# l298.net
KiCad netlist of a schematic drawn in EAGLE
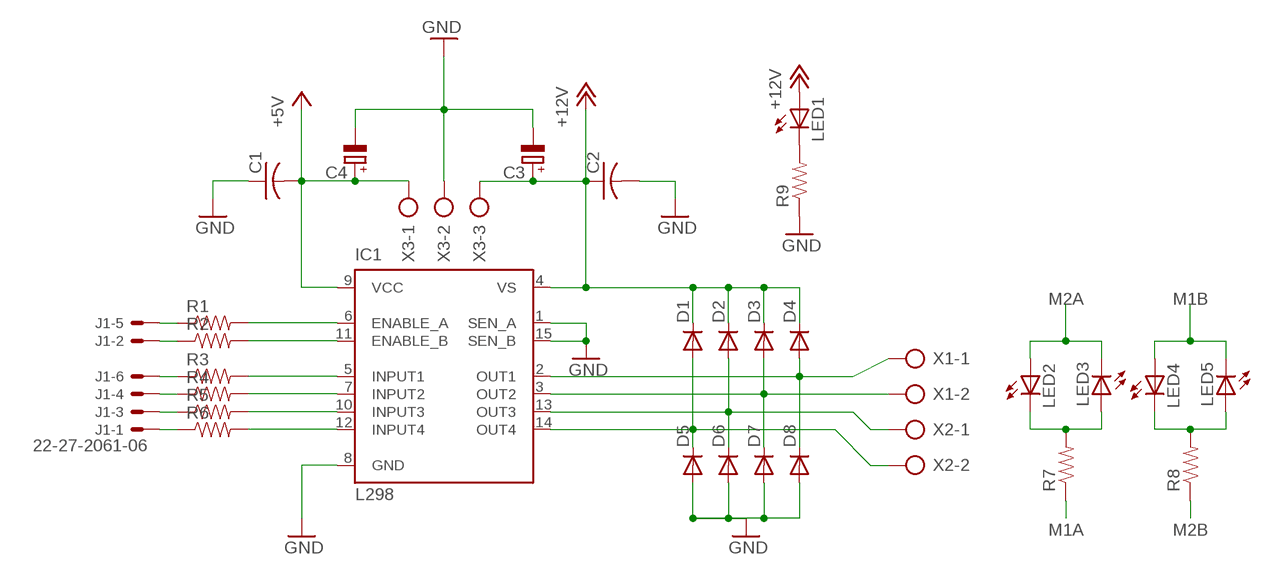
[diagram p0: schematic, sheet 1]

(export (version "E")
  (design (tool "Eeschema 10.0.6"))
  (components
    (comp (ref "C1")
      (value "C-US025-024X044")
      (footprint "eagle-import:C025-024X044")
      (libsource (lib "eagle-import") (part "C-US025-024X044"))
    )
    (comp (ref "C2")
      (value "C-US025-024X044")
      (footprint "eagle-import:C025-024X044")
      (libsource (lib "eagle-import") (part "C-US025-024X044"))
    )
    (comp (ref "C3")
      (value "CPOL-EUE5-10.5")
      (footprint "eagle-import:E5-10,5")
      (libsource (lib "eagle-import") (part "CPOL-EUE5-10.5"))
    )
    (comp (ref "C4")
      (value "CPOL-EUE2-5")
      (footprint "eagle-import:E2-5")
      (libsource (lib "eagle-import") (part "CPOL-EUE2-5"))
    )
    (comp (ref "D1")
      (value "DIODE1N4148")
      (footprint "eagle-import:DIODE-1N4148")
      (libsource (lib "eagle-import") (part "DIODE1N4148"))
    )
    (comp (ref "D2")
      (value "DIODE1N4148")
      (footprint "eagle-import:DIODE-1N4148")
      (libsource (lib "eagle-import") (part "DIODE1N4148"))
    )
    (comp (ref "D3")
      (value "DIODE1N4148")
      (footprint "eagle-import:DIODE-1N4148")
      (libsource (lib "eagle-import") (part "DIODE1N4148"))
    )
    (comp (ref "D4")
      (value "DIODE1N4148")
      (footprint "eagle-import:DIODE-1N4148")
      (libsource (lib "eagle-import") (part "DIODE1N4148"))
    )
    (comp (ref "D5")
      (value "DIODE1N4148")
      (footprint "eagle-import:DIODE-1N4148")
      (libsource (lib "eagle-import") (part "DIODE1N4148"))
    )
    (comp (ref "D6")
      (value "DIODE1N4148")
      (footprint "eagle-import:DIODE-1N4148")
      (libsource (lib "eagle-import") (part "DIODE1N4148"))
    )
    (comp (ref "D7")
      (value "DIODE1N4148")
      (footprint "eagle-import:DIODE-1N4148")
      (libsource (lib "eagle-import") (part "DIODE1N4148"))
    )
    (comp (ref "D8")
      (value "DIODE1N4148")
      (footprint "eagle-import:DIODE-1N4148")
      (libsource (lib "eagle-import") (part "DIODE1N4148"))
    )
    (comp (ref "IC1")
      (value "L298")
      (footprint "eagle-import:MULTIWATT-15")
      (libsource (lib "eagle-import") (part "L298"))
    )
    (comp (ref "J1")
      (value "22-27-2061-06")
      (footprint "eagle-import:6410-06")
      (libsource (lib "eagle-import") (part "22-?-0627-2061"))
    )
    (comp (ref "LED1")
      (value "LED3MM")
      (footprint "eagle-import:LED3MM")
      (libsource (lib "eagle-import") (part "LED3MM"))
    )
    (comp (ref "LED2")
      (value "LED3MM")
      (footprint "eagle-import:LED3MM")
      (libsource (lib "eagle-import") (part "LED3MM"))
    )
    (comp (ref "LED3")
      (value "LED3MM")
      (footprint "eagle-import:LED3MM")
      (libsource (lib "eagle-import") (part "LED3MM"))
    )
    (comp (ref "LED4")
      (value "LED3MM")
      (footprint "eagle-import:LED3MM")
      (libsource (lib "eagle-import") (part "LED3MM"))
    )
    (comp (ref "LED5")
      (value "LED3MM")
      (footprint "eagle-import:LED3MM")
      (libsource (lib "eagle-import") (part "LED3MM"))
    )
    (comp (ref "R1")
      (value "RESISTORPTH-1/6W")
      (footprint "eagle-import:1_6W-RES")
      (libsource (lib "eagle-import") (part "RESISTORPTH-1/6W"))
    )
    (comp (ref "R2")
      (value "RESISTORPTH-1/6W")
      (footprint "eagle-import:1_6W-RES")
      (libsource (lib "eagle-import") (part "RESISTORPTH-1/6W"))
    )
    (comp (ref "R3")
      (value "RESISTORPTH-1/6W")
      (footprint "eagle-import:1_6W-RES")
      (libsource (lib "eagle-import") (part "RESISTORPTH-1/6W"))
    )
    (comp (ref "R4")
      (value "RESISTORPTH-1/6W")
      (footprint "eagle-import:1_6W-RES")
      (libsource (lib "eagle-import") (part "RESISTORPTH-1/6W"))
    )
    (comp (ref "R5")
      (value "RESISTORPTH-1/6W")
      (footprint "eagle-import:1_6W-RES")
      (libsource (lib "eagle-import") (part "RESISTORPTH-1/6W"))
    )
    (comp (ref "R6")
      (value "RESISTORPTH-1/6W")
      (footprint "eagle-import:1_6W-RES")
      (libsource (lib "eagle-import") (part "RESISTORPTH-1/6W"))
    )
    (comp (ref "R7")
      (value "RESISTORPTH-1/6W")
      (footprint "eagle-import:1_6W-RES")
      (libsource (lib "eagle-import") (part "RESISTORPTH-1/6W"))
    )
    (comp (ref "R8")
      (value "RESISTORPTH-1/6W")
      (footprint "eagle-import:1_6W-RES")
      (libsource (lib "eagle-import") (part "RESISTORPTH-1/6W"))
    )
    (comp (ref "R9")
      (value "RESISTORPTH-1/6W")
      (footprint "eagle-import:1_6W-RES")
      (libsource (lib "eagle-import") (part "RESISTORPTH-1/6W"))
    )
    (comp (ref "X1")
      (value "AK500/2")
      (footprint "eagle-import:AK500_2")
      (libsource (lib "eagle-import") (part "AK500/2"))
    )
    (comp (ref "X2")
      (value "AK500/2")
      (footprint "eagle-import:AK500_2")
      (libsource (lib "eagle-import") (part "AK500/2"))
    )
    (comp (ref "X3")
      (value "AK500/3")
      (footprint "eagle-import:AK500_3")
      (libsource (lib "eagle-import") (part "AK500/3"))
    )
  )
  (nets
    (net (code "1") (name "+5V") (class "Default")
      (node (ref "C1") (pin "2") (pinfunction "2_2") (pintype "passive"))
      (node (ref "C4") (pin "+") (pinfunction "+_+") (pintype "passive"))
      (node (ref "IC1") (pin "9") (pinfunction "VCC_9") (pintype "power_in"))
      (node (ref "X3") (pin "1") (pinfunction "KL_1") (pintype "passive"))
    )
    (net (code "2") (name "+12V") (class "Default")
      (node (ref "C2") (pin "1") (pinfunction "1_1") (pintype "passive"))
      (node (ref "C3") (pin "+") (pinfunction "+_+") (pintype "passive"))
      (node (ref "D1") (pin "C") (pinfunction "C_C") (pintype "passive"))
      (node (ref "D2") (pin "C") (pinfunction "C_C") (pintype "passive"))
      (node (ref "D3") (pin "C") (pinfunction "C_C") (pintype "passive"))
      (node (ref "D4") (pin "C") (pinfunction "C_C") (pintype "passive"))
      (node (ref "IC1") (pin "4") (pinfunction "VS_4") (pintype "power_in"))
      (node (ref "LED1") (pin "A") (pinfunction "A_A") (pintype "passive"))
      (node (ref "X3") (pin "3") (pinfunction "KL_3") (pintype "passive"))
    )
    (net (code "3") (name "/M1A") (class "Default")
      (node (ref "D4") (pin "A") (pinfunction "A_A") (pintype "passive"))
      (node (ref "D8") (pin "C") (pinfunction "C_C") (pintype "passive"))
      (node (ref "IC1") (pin "2") (pinfunction "OUT1_2") (pintype "output"))
      (node (ref "R7") (pin "1") (pinfunction "1_1") (pintype "passive"))
      (node (ref "X1") (pin "1") (pinfunction "KL_1") (pintype "passive"))
    )
    (net (code "4") (name "/M1B") (class "Default")
      (node (ref "D2") (pin "A") (pinfunction "A_A") (pintype "passive"))
      (node (ref "D6") (pin "C") (pinfunction "C_C") (pintype "passive"))
      (node (ref "IC1") (pin "13") (pinfunction "OUT3_13") (pintype "output"))
      (node (ref "LED4") (pin "A") (pinfunction "A_A") (pintype "passive"))
      (node (ref "LED5") (pin "K") (pinfunction "C_K") (pintype "passive"))
      (node (ref "X2") (pin "1") (pinfunction "KL_1") (pintype "passive"))
    )
    (net (code "5") (name "/M2A") (class "Default")
      (node (ref "D3") (pin "A") (pinfunction "A_A") (pintype "passive"))
      (node (ref "D7") (pin "C") (pinfunction "C_C") (pintype "passive"))
      (node (ref "IC1") (pin "3") (pinfunction "OUT2_3") (pintype "output"))
      (node (ref "LED2") (pin "A") (pinfunction "A_A") (pintype "passive"))
      (node (ref "LED3") (pin "K") (pinfunction "C_K") (pintype "passive"))
      (node (ref "X1") (pin "2") (pinfunction "KL_2") (pintype "passive"))
    )
    (net (code "6") (name "/M2B") (class "Default")
      (node (ref "D1") (pin "A") (pinfunction "A_A") (pintype "passive"))
      (node (ref "D5") (pin "C") (pinfunction "C_C") (pintype "passive"))
      (node (ref "IC1") (pin "14") (pinfunction "OUT4_14") (pintype "output"))
      (node (ref "R8") (pin "1") (pinfunction "1_1") (pintype "passive"))
      (node (ref "X2") (pin "2") (pinfunction "KL_2") (pintype "passive"))
    )
    (net (code "7") (name "GND") (class "Default")
      (node (ref "C1") (pin "1") (pinfunction "1_1") (pintype "passive"))
      (node (ref "C2") (pin "2") (pinfunction "2_2") (pintype "passive"))
      (node (ref "C3") (pin "-") (pinfunction "-_-") (pintype "passive"))
      (node (ref "C4") (pin "-") (pinfunction "-_-") (pintype "passive"))
      (node (ref "D5") (pin "A") (pinfunction "A_A") (pintype "passive"))
      (node (ref "D6") (pin "A") (pinfunction "A_A") (pintype "passive"))
      (node (ref "D7") (pin "A") (pinfunction "A_A") (pintype "passive"))
      (node (ref "D8") (pin "A") (pinfunction "A_A") (pintype "passive"))
      (node (ref "IC1") (pin "1") (pinfunction "SEN_A_1") (pintype "input"))
      (node (ref "IC1") (pin "15") (pinfunction "SEN_B_15") (pintype "input"))
      (node (ref "IC1") (pin "8") (pinfunction "GND_8") (pintype "power_in"))
      (node (ref "R9") (pin "1") (pinfunction "1_1") (pintype "passive"))
      (node (ref "X3") (pin "2") (pinfunction "KL_2") (pintype "passive"))
    )
    (net (code "8") (name "Net-(IC1-ENABLE_A)") (class "Default")
      (node (ref "IC1") (pin "6") (pinfunction "ENABLE_A_6") (pintype "input"))
      (node (ref "R1") (pin "2") (pinfunction "2_2") (pintype "passive"))
    )
    (net (code "9") (name "Net-(IC1-ENABLE_B)") (class "Default")
      (node (ref "IC1") (pin "11") (pinfunction "ENABLE_B_11") (pintype "input"))
      (node (ref "R2") (pin "2") (pinfunction "2_2") (pintype "passive"))
    )
    (net (code "10") (name "Net-(IC1-INPUT1)") (class "Default")
      (node (ref "IC1") (pin "5") (pinfunction "INPUT1_5") (pintype "input"))
      (node (ref "R3") (pin "2") (pinfunction "2_2") (pintype "passive"))
    )
    (net (code "11") (name "Net-(IC1-INPUT2)") (class "Default")
      (node (ref "IC1") (pin "7") (pinfunction "INPUT2_7") (pintype "input"))
      (node (ref "R4") (pin "2") (pinfunction "2_2") (pintype "passive"))
    )
    (net (code "12") (name "Net-(IC1-INPUT3)") (class "Default")
      (node (ref "IC1") (pin "10") (pinfunction "INPUT3_10") (pintype "input"))
      (node (ref "R5") (pin "2") (pinfunction "2_2") (pintype "passive"))
    )
    (net (code "13") (name "Net-(IC1-INPUT4)") (class "Default")
      (node (ref "IC1") (pin "12") (pinfunction "INPUT4_12") (pintype "input"))
      (node (ref "R6") (pin "2") (pinfunction "2_2") (pintype "passive"))
    )
    (net (code "14") (name "Net-(J1A-S)") (class "Default")
      (node (ref "J1") (pin "1") (pinfunction "S_1") (pintype "passive"))
      (node (ref "R6") (pin "1") (pinfunction "1_1") (pintype "passive"))
    )
    (net (code "15") (name "Net-(J1B-S)") (class "Default")
      (node (ref "J1") (pin "2") (pinfunction "S_2") (pintype "passive"))
      (node (ref "R2") (pin "1") (pinfunction "1_1") (pintype "passive"))
    )
    (net (code "16") (name "Net-(J1C-S)") (class "Default")
      (node (ref "J1") (pin "3") (pinfunction "S_3") (pintype "passive"))
      (node (ref "R5") (pin "1") (pinfunction "1_1") (pintype "passive"))
    )
    (net (code "17") (name "Net-(J1D-S)") (class "Default")
      (node (ref "J1") (pin "4") (pinfunction "S_4") (pintype "passive"))
      (node (ref "R4") (pin "1") (pinfunction "1_1") (pintype "passive"))
    )
    (net (code "18") (name "Net-(J1E-S)") (class "Default")
      (node (ref "J1") (pin "5") (pinfunction "S_5") (pintype "passive"))
      (node (ref "R1") (pin "1") (pinfunction "1_1") (pintype "passive"))
    )
    (net (code "19") (name "Net-(J1F-S)") (class "Default")
      (node (ref "J1") (pin "6") (pinfunction "S_6") (pintype "passive"))
      (node (ref "R3") (pin "1") (pinfunction "1_1") (pintype "passive"))
    )
    (net (code "20") (name "Net-(LED1-C)") (class "Default")
      (node (ref "LED1") (pin "K") (pinfunction "C_K") (pintype "passive"))
      (node (ref "R9") (pin "2") (pinfunction "2_2") (pintype "passive"))
    )
    (net (code "21") (name "Net-(LED2-C)") (class "Default")
      (node (ref "LED2") (pin "K") (pinfunction "C_K") (pintype "passive"))
      (node (ref "LED3") (pin "A") (pinfunction "A_A") (pintype "passive"))
      (node (ref "R7") (pin "2") (pinfunction "2_2") (pintype "passive"))
    )
    (net (code "22") (name "Net-(LED4-C)") (class "Default")
      (node (ref "LED4") (pin "K") (pinfunction "C_K") (pintype "passive"))
      (node (ref "LED5") (pin "A") (pinfunction "A_A") (pintype "passive"))
      (node (ref "R8") (pin "2") (pinfunction "2_2") (pintype "passive"))
    )
  )
)
